# ES9023.net
KiCad netlist of a schematic drawn in EAGLE
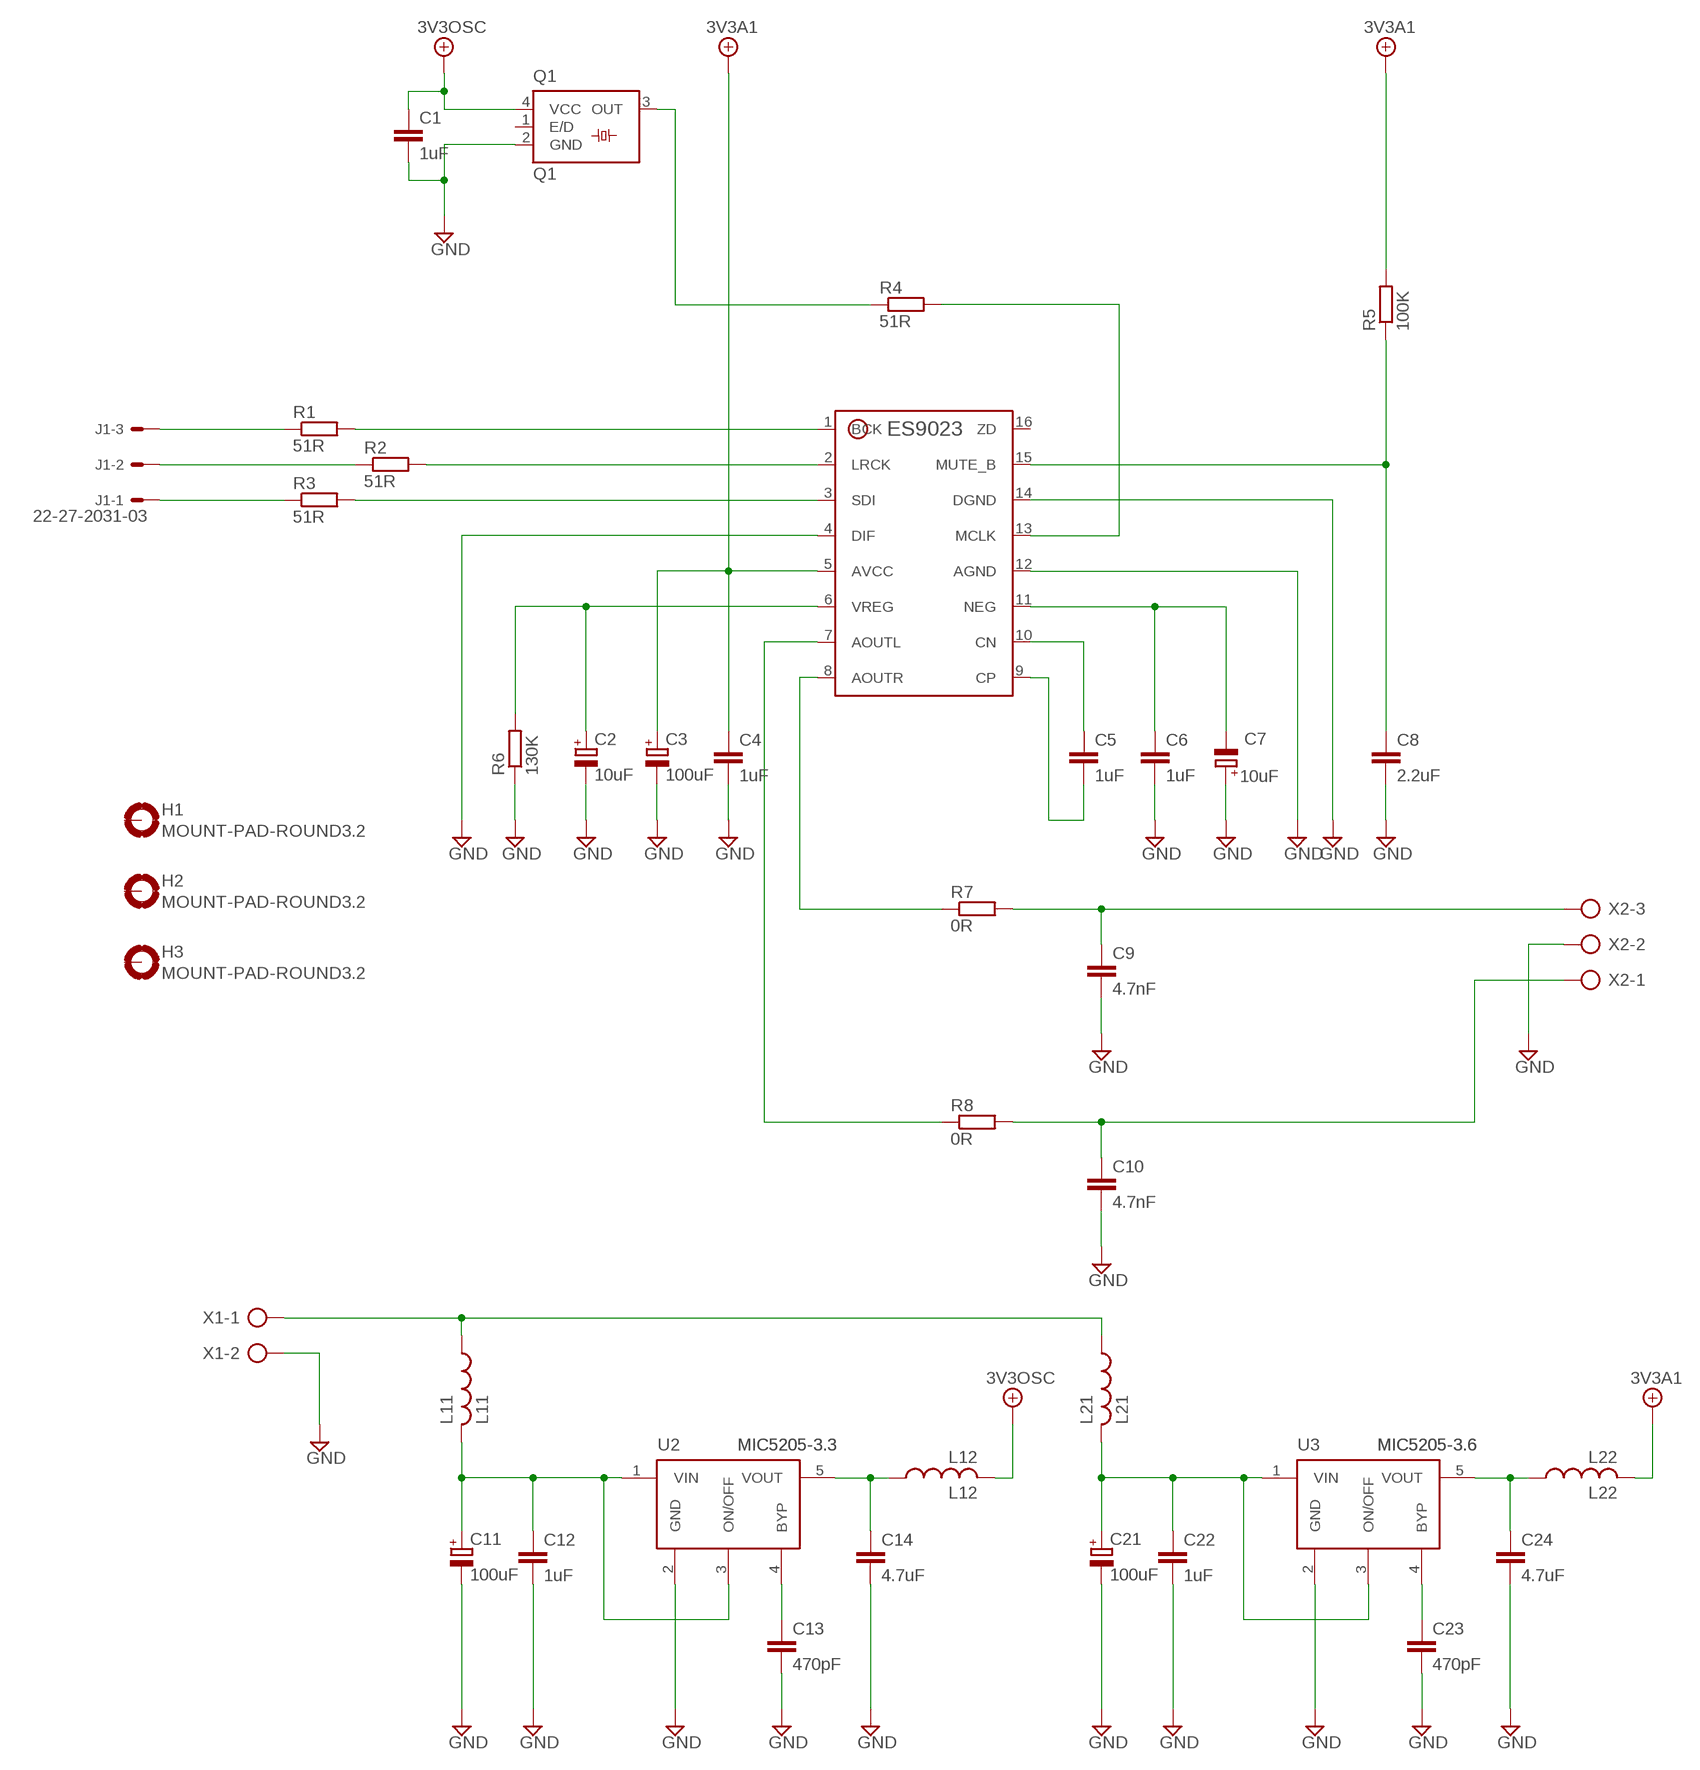
[diagram p0: schematic, sheet 1]

(export (version "E")
  (design (tool "Eeschema 10.0.6"))
  (components
    (comp (ref "C1")
      (value "1uF")
      (footprint "eagle-import:C1210")
      (libsource (lib "eagle-import") (part "CAPACITORC1210"))
    )
    (comp (ref "C2")
      (value "10uF")
      (footprint "eagle-import:E2,5-5")
      (libsource (lib "eagle-import") (part "CAP-POLE2.5-5"))
    )
    (comp (ref "C3")
      (value "100uF")
      (footprint "eagle-import:E2,5-5")
      (libsource (lib "eagle-import") (part "CAP-POLE2.5-5"))
    )
    (comp (ref "C4")
      (value "1uF")
      (footprint "eagle-import:C1210")
      (libsource (lib "eagle-import") (part "CAPACITORC1210"))
    )
    (comp (ref "C5")
      (value "1uF")
      (footprint "eagle-import:C1210")
      (libsource (lib "eagle-import") (part "CAPACITORC1210"))
    )
    (comp (ref "C6")
      (value "1uF")
      (footprint "eagle-import:C1210")
      (libsource (lib "eagle-import") (part "CAPACITORC1210"))
    )
    (comp (ref "C7")
      (value "10uF")
      (footprint "eagle-import:E2,5-5")
      (libsource (lib "eagle-import") (part "CAP-POLE2.5-5"))
    )
    (comp (ref "C8")
      (value "2.2uF")
      (footprint "eagle-import:C0805")
      (libsource (lib "eagle-import") (part "CAPACITORC0805"))
    )
    (comp (ref "C9")
      (value "4.7nF")
      (footprint "eagle-import:5.08MM")
      (libsource (lib "eagle-import") (part "CAPACITOR5.08MM"))
    )
    (comp (ref "C10")
      (value "4.7nF")
      (footprint "eagle-import:5.08MM")
      (libsource (lib "eagle-import") (part "CAPACITOR5.08MM"))
    )
    (comp (ref "C11")
      (value "100uF")
      (footprint "eagle-import:E2,5-5")
      (libsource (lib "eagle-import") (part "CAP-POLE2.5-5"))
    )
    (comp (ref "C12")
      (value "1uF")
      (footprint "eagle-import:C1210")
      (libsource (lib "eagle-import") (part "CAPACITORC1210"))
    )
    (comp (ref "C13")
      (value "470pF")
      (footprint "eagle-import:C0805")
      (libsource (lib "eagle-import") (part "CAPACITORC0805"))
    )
    (comp (ref "C14")
      (value "4.7uF")
      (footprint "eagle-import:C1210")
      (libsource (lib "eagle-import") (part "CAPACITORC1210"))
    )
    (comp (ref "C21")
      (value "100uF")
      (footprint "eagle-import:E2,5-5")
      (libsource (lib "eagle-import") (part "CAP-POLE2.5-5"))
    )
    (comp (ref "C22")
      (value "1uF")
      (footprint "eagle-import:C1210")
      (libsource (lib "eagle-import") (part "CAPACITORC1210"))
    )
    (comp (ref "C23")
      (value "470pF")
      (footprint "eagle-import:C0805")
      (libsource (lib "eagle-import") (part "CAPACITORC0805"))
    )
    (comp (ref "C24")
      (value "4.7uF")
      (footprint "eagle-import:C1210")
      (libsource (lib "eagle-import") (part "CAPACITORC1210"))
    )
    (comp (ref "H1")
      (value "MOUNT-PAD-ROUND3.2")
      (footprint "eagle-import:3,2-PAD")
      (libsource (lib "eagle-import") (part "MOUNT-PAD-ROUND3.2"))
    )
    (comp (ref "H2")
      (value "MOUNT-PAD-ROUND3.2")
      (footprint "eagle-import:3,2-PAD")
      (libsource (lib "eagle-import") (part "MOUNT-PAD-ROUND3.2"))
    )
    (comp (ref "H3")
      (value "MOUNT-PAD-ROUND3.2")
      (footprint "eagle-import:3,2-PAD")
      (libsource (lib "eagle-import") (part "MOUNT-PAD-ROUND3.2"))
    )
    (comp (ref "J1")
      (value "22-27-2031-03")
      (footprint "eagle-import:6410-03")
      (libsource (lib "eagle-import") (part "22-?-0327-2031"))
    )
    (comp (ref "L11")
      (value "L11")
      (footprint "eagle-import:1812")
      (libsource (lib "eagle-import") (part "INDUCTOR1812"))
    )
    (comp (ref "L12")
      (value "L12")
      (footprint "eagle-import:R1206")
      (libsource (lib "eagle-import") (part "INDUCTORR1206"))
    )
    (comp (ref "L21")
      (value "L21")
      (footprint "eagle-import:1812")
      (libsource (lib "eagle-import") (part "INDUCTOR1812"))
    )
    (comp (ref "L22")
      (value "L22")
      (footprint "eagle-import:R1206")
      (libsource (lib "eagle-import") (part "INDUCTORR1206"))
    )
    (comp (ref "Q1")
      (value "Q1")
      (footprint "eagle-import:SM77H")
      (libsource (lib "eagle-import") (part "OSCILLATOR50MHZ"))
    )
    (comp (ref "R1")
      (value "51R")
      (footprint "eagle-import:R0805")
      (libsource (lib "eagle-import") (part "RESISTORR0805"))
    )
    (comp (ref "R2")
      (value "51R")
      (footprint "eagle-import:R0805")
      (libsource (lib "eagle-import") (part "RESISTORR0805"))
    )
    (comp (ref "R3")
      (value "51R")
      (footprint "eagle-import:R0805")
      (libsource (lib "eagle-import") (part "RESISTORR0805"))
    )
    (comp (ref "R4")
      (value "51R")
      (footprint "eagle-import:R0805")
      (libsource (lib "eagle-import") (part "RESISTORR0805"))
    )
    (comp (ref "R5")
      (value "100K")
      (footprint "eagle-import:R0805")
      (libsource (lib "eagle-import") (part "RESISTORR0805"))
    )
    (comp (ref "R6")
      (value "130K")
      (footprint "eagle-import:R0805")
      (libsource (lib "eagle-import") (part "RESISTORR0805"))
    )
    (comp (ref "R7")
      (value "0R")
      (footprint "eagle-import:R0805")
      (libsource (lib "eagle-import") (part "RESISTORR0805"))
    )
    (comp (ref "R8")
      (value "0R")
      (footprint "eagle-import:R0805")
      (libsource (lib "eagle-import") (part "RESISTORR0805"))
    )
    (comp (ref "U1")
      (value "ES9023")
      (footprint "eagle-import:SOP-16")
      (libsource (lib "eagle-import") (part "ES9023"))
    )
    (comp (ref "U2")
      (value "MIC5205-3.3")
      (footprint "eagle-import:SOT23-5")
      (libsource (lib "eagle-import") (part "MIC5205"))
    )
    (comp (ref "U3")
      (value "MIC5205-3.6")
      (footprint "eagle-import:SOT23-5")
      (libsource (lib "eagle-import") (part "MIC5205"))
    )
    (comp (ref "X1")
      (value "AK300/2")
      (footprint "eagle-import:AK300_2")
      (libsource (lib "eagle-import") (part "AK300/2"))
    )
    (comp (ref "X2")
      (value "AK300/3")
      (footprint "eagle-import:AK300_3")
      (libsource (lib "eagle-import") (part "AK300/3"))
    )
  )
  (nets
    (net (code "1") (name "3V3A1") (class "Default")
      (node (ref "C3") (pin "+") (pinfunction "+_+") (pintype "passive"))
      (node (ref "C4") (pin "1") (pinfunction "1_1") (pintype "passive"))
      (node (ref "L22") (pin "2") (pinfunction "2_2") (pintype "passive"))
      (node (ref "R5") (pin "2") (pinfunction "2_2") (pintype "passive"))
      (node (ref "U1") (pin "5") (pinfunction "AVCC_5") (pintype "bidirectional"))
    )
    (net (code "2") (name "3V3OSC") (class "Default")
      (node (ref "C1") (pin "1") (pinfunction "1_1") (pintype "passive"))
      (node (ref "L12") (pin "2") (pinfunction "2_2") (pintype "passive"))
      (node (ref "Q1") (pin "4") (pinfunction "VCC_4") (pintype "power_in"))
    )
    (net (code "3") (name "GND") (class "Default")
      (node (ref "C1") (pin "2") (pinfunction "2_2") (pintype "passive"))
      (node (ref "C10") (pin "2") (pinfunction "2_2") (pintype "passive"))
      (node (ref "C11") (pin "-") (pinfunction "-_-") (pintype "passive"))
      (node (ref "C12") (pin "2") (pinfunction "2_2") (pintype "passive"))
      (node (ref "C13") (pin "2") (pinfunction "2_2") (pintype "passive"))
      (node (ref "C14") (pin "2") (pinfunction "2_2") (pintype "passive"))
      (node (ref "C2") (pin "-") (pinfunction "-_-") (pintype "passive"))
      (node (ref "C21") (pin "-") (pinfunction "-_-") (pintype "passive"))
      (node (ref "C22") (pin "2") (pinfunction "2_2") (pintype "passive"))
      (node (ref "C23") (pin "2") (pinfunction "2_2") (pintype "passive"))
      (node (ref "C24") (pin "2") (pinfunction "2_2") (pintype "passive"))
      (node (ref "C3") (pin "-") (pinfunction "-_-") (pintype "passive"))
      (node (ref "C4") (pin "2") (pinfunction "2_2") (pintype "passive"))
      (node (ref "C6") (pin "2") (pinfunction "2_2") (pintype "passive"))
      (node (ref "C7") (pin "+") (pinfunction "+_+") (pintype "passive"))
      (node (ref "C8") (pin "2") (pinfunction "2_2") (pintype "passive"))
      (node (ref "C9") (pin "2") (pinfunction "2_2") (pintype "passive"))
      (node (ref "Q1") (pin "2") (pinfunction "GND_2") (pintype "power_in"))
      (node (ref "R6") (pin "1") (pinfunction "1_1") (pintype "passive"))
      (node (ref "U1") (pin "12") (pinfunction "AGND_12") (pintype "bidirectional"))
      (node (ref "U1") (pin "14") (pinfunction "DGND_14") (pintype "bidirectional"))
      (node (ref "U1") (pin "4") (pinfunction "DIF_4") (pintype "bidirectional"))
      (node (ref "U2") (pin "2") (pinfunction "GND_2") (pintype "bidirectional"))
      (node (ref "U3") (pin "2") (pinfunction "GND_2") (pintype "bidirectional"))
      (node (ref "X1") (pin "2") (pinfunction "KL_2") (pintype "passive"))
      (node (ref "X2") (pin "2") (pinfunction "KL_2") (pintype "passive"))
    )
    (net (code "4") (name "Net-(J1A-S)") (class "Default")
      (node (ref "J1") (pin "1") (pinfunction "S_1") (pintype "passive"))
      (node (ref "R3") (pin "1") (pinfunction "1_1") (pintype "passive"))
    )
    (net (code "5") (name "Net-(J1B-S)") (class "Default")
      (node (ref "J1") (pin "2") (pinfunction "S_2") (pintype "passive"))
      (node (ref "R2") (pin "1") (pinfunction "1_1") (pintype "passive"))
    )
    (net (code "6") (name "Net-(J1C-S)") (class "Default")
      (node (ref "J1") (pin "3") (pinfunction "S_3") (pintype "passive"))
      (node (ref "R1") (pin "1") (pinfunction "1_1") (pintype "passive"))
    )
    (net (code "7") (name "Net-(Q1-OUT)") (class "Default")
      (node (ref "Q1") (pin "3") (pinfunction "OUT_3") (pintype "output"))
      (node (ref "R4") (pin "1") (pinfunction "1_1") (pintype "passive"))
    )
    (net (code "8") (name "Net-(U1-AOUTL)") (class "Default")
      (node (ref "R8") (pin "1") (pinfunction "1_1") (pintype "passive"))
      (node (ref "U1") (pin "7") (pinfunction "AOUTL_7") (pintype "bidirectional"))
    )
    (net (code "9") (name "Net-(U1-AOUTR)") (class "Default")
      (node (ref "R7") (pin "1") (pinfunction "1_1") (pintype "passive"))
      (node (ref "U1") (pin "8") (pinfunction "AOUTR_8") (pintype "bidirectional"))
    )
    (net (code "10") (name "Net-(U1-BCK)") (class "Default")
      (node (ref "R1") (pin "2") (pinfunction "2_2") (pintype "passive"))
      (node (ref "U1") (pin "1") (pinfunction "BCK_1") (pintype "bidirectional"))
    )
    (net (code "11") (name "Net-(U1-CN)") (class "Default")
      (node (ref "C5") (pin "1") (pinfunction "1_1") (pintype "passive"))
      (node (ref "U1") (pin "10") (pinfunction "CN_10") (pintype "bidirectional"))
    )
    (net (code "12") (name "Net-(U1-CP)") (class "Default")
      (node (ref "C5") (pin "2") (pinfunction "2_2") (pintype "passive"))
      (node (ref "U1") (pin "9") (pinfunction "CP_9") (pintype "bidirectional"))
    )
    (net (code "13") (name "Net-(U1-LRCK)") (class "Default")
      (node (ref "R2") (pin "2") (pinfunction "2_2") (pintype "passive"))
      (node (ref "U1") (pin "2") (pinfunction "LRCK_2") (pintype "bidirectional"))
    )
    (net (code "14") (name "Net-(U1-MCLK)") (class "Default")
      (node (ref "R4") (pin "2") (pinfunction "2_2") (pintype "passive"))
      (node (ref "U1") (pin "13") (pinfunction "MCLK_13") (pintype "bidirectional"))
    )
    (net (code "15") (name "Net-(U1-MUTE_B)") (class "Default")
      (node (ref "C8") (pin "1") (pinfunction "1_1") (pintype "passive"))
      (node (ref "R5") (pin "1") (pinfunction "1_1") (pintype "passive"))
      (node (ref "U1") (pin "15") (pinfunction "MUTE_B_15") (pintype "bidirectional"))
    )
    (net (code "16") (name "Net-(U1-NEG)") (class "Default")
      (node (ref "C6") (pin "1") (pinfunction "1_1") (pintype "passive"))
      (node (ref "C7") (pin "-") (pinfunction "-_-") (pintype "passive"))
      (node (ref "U1") (pin "11") (pinfunction "NEG_11") (pintype "bidirectional"))
    )
    (net (code "17") (name "Net-(U1-SDI)") (class "Default")
      (node (ref "R3") (pin "2") (pinfunction "2_2") (pintype "passive"))
      (node (ref "U1") (pin "3") (pinfunction "SDI_3") (pintype "bidirectional"))
    )
    (net (code "18") (name "Net-(U1-VREG)") (class "Default")
      (node (ref "C2") (pin "+") (pinfunction "+_+") (pintype "passive"))
      (node (ref "R6") (pin "2") (pinfunction "2_2") (pintype "passive"))
      (node (ref "U1") (pin "6") (pinfunction "VREG_6") (pintype "bidirectional"))
    )
    (net (code "19") (name "Net-(U2-BYP)") (class "Default")
      (node (ref "C13") (pin "1") (pinfunction "1_1") (pintype "passive"))
      (node (ref "U2") (pin "4") (pinfunction "BYP_4") (pintype "bidirectional"))
    )
    (net (code "20") (name "Net-(U2-ON{slash}OFF)") (class "Default")
      (node (ref "C11") (pin "+") (pinfunction "+_+") (pintype "passive"))
      (node (ref "C12") (pin "1") (pinfunction "1_1") (pintype "passive"))
      (node (ref "L11") (pin "2") (pinfunction "2_2") (pintype "passive"))
      (node (ref "U2") (pin "1") (pinfunction "VIN_1") (pintype "bidirectional"))
      (node (ref "U2") (pin "3") (pinfunction "ON/OFF_3") (pintype "bidirectional"))
    )
    (net (code "21") (name "Net-(U2-VOUT)") (class "Default")
      (node (ref "C14") (pin "1") (pinfunction "1_1") (pintype "passive"))
      (node (ref "L12") (pin "1") (pinfunction "1_1") (pintype "passive"))
      (node (ref "U2") (pin "5") (pinfunction "VOUT_5") (pintype "bidirectional"))
    )
    (net (code "22") (name "Net-(U3-BYP)") (class "Default")
      (node (ref "C23") (pin "1") (pinfunction "1_1") (pintype "passive"))
      (node (ref "U3") (pin "4") (pinfunction "BYP_4") (pintype "bidirectional"))
    )
    (net (code "23") (name "Net-(U3-ON{slash}OFF)") (class "Default")
      (node (ref "C21") (pin "+") (pinfunction "+_+") (pintype "passive"))
      (node (ref "C22") (pin "1") (pinfunction "1_1") (pintype "passive"))
      (node (ref "L21") (pin "2") (pinfunction "2_2") (pintype "passive"))
      (node (ref "U3") (pin "1") (pinfunction "VIN_1") (pintype "bidirectional"))
      (node (ref "U3") (pin "3") (pinfunction "ON/OFF_3") (pintype "bidirectional"))
    )
    (net (code "24") (name "Net-(U3-VOUT)") (class "Default")
      (node (ref "C24") (pin "1") (pinfunction "1_1") (pintype "passive"))
      (node (ref "L22") (pin "1") (pinfunction "1_1") (pintype "passive"))
      (node (ref "U3") (pin "5") (pinfunction "VOUT_5") (pintype "bidirectional"))
    )
    (net (code "25") (name "Net-(X1A-KL)") (class "Default")
      (node (ref "L11") (pin "1") (pinfunction "1_1") (pintype "passive"))
      (node (ref "L21") (pin "1") (pinfunction "1_1") (pintype "passive"))
      (node (ref "X1") (pin "1") (pinfunction "KL_1") (pintype "passive"))
    )
    (net (code "26") (name "Net-(X2A-KL)") (class "Default")
      (node (ref "C10") (pin "1") (pinfunction "1_1") (pintype "passive"))
      (node (ref "R8") (pin "2") (pinfunction "2_2") (pintype "passive"))
      (node (ref "X2") (pin "1") (pinfunction "KL_1") (pintype "passive"))
    )
    (net (code "27") (name "Net-(X2C-KL)") (class "Default")
      (node (ref "C9") (pin "1") (pinfunction "1_1") (pintype "passive"))
      (node (ref "R7") (pin "2") (pinfunction "2_2") (pintype "passive"))
      (node (ref "X2") (pin "3") (pinfunction "KL_3") (pintype "passive"))
    )
    (net (code "28") (name "unconnected-(H1-MOUNT-PadB3,2)") (class "Default")
      (node (ref "H1") (pin "B3,2") (pinfunction "MOUNT_B3,2") (pintype "passive"))
    )
    (net (code "29") (name "unconnected-(H2-MOUNT-PadB3,2)") (class "Default")
      (node (ref "H2") (pin "B3,2") (pinfunction "MOUNT_B3,2") (pintype "passive"))
    )
    (net (code "30") (name "unconnected-(H3-MOUNT-PadB3,2)") (class "Default")
      (node (ref "H3") (pin "B3,2") (pinfunction "MOUNT_B3,2") (pintype "passive"))
    )
    (net (code "31") (name "unconnected-(Q1-E{slash}D-Pad1)") (class "Default")
      (node (ref "Q1") (pin "1") (pinfunction "E/D_1") (pintype "input"))
    )
    (net (code "32") (name "unconnected-(U1-ZD-Pad16)") (class "Default")
      (node (ref "U1") (pin "16") (pinfunction "ZD_16") (pintype "bidirectional"))
    )
  )
)
